# yarns_v03.net
KiCad netlist of a schematic drawn in EAGLE
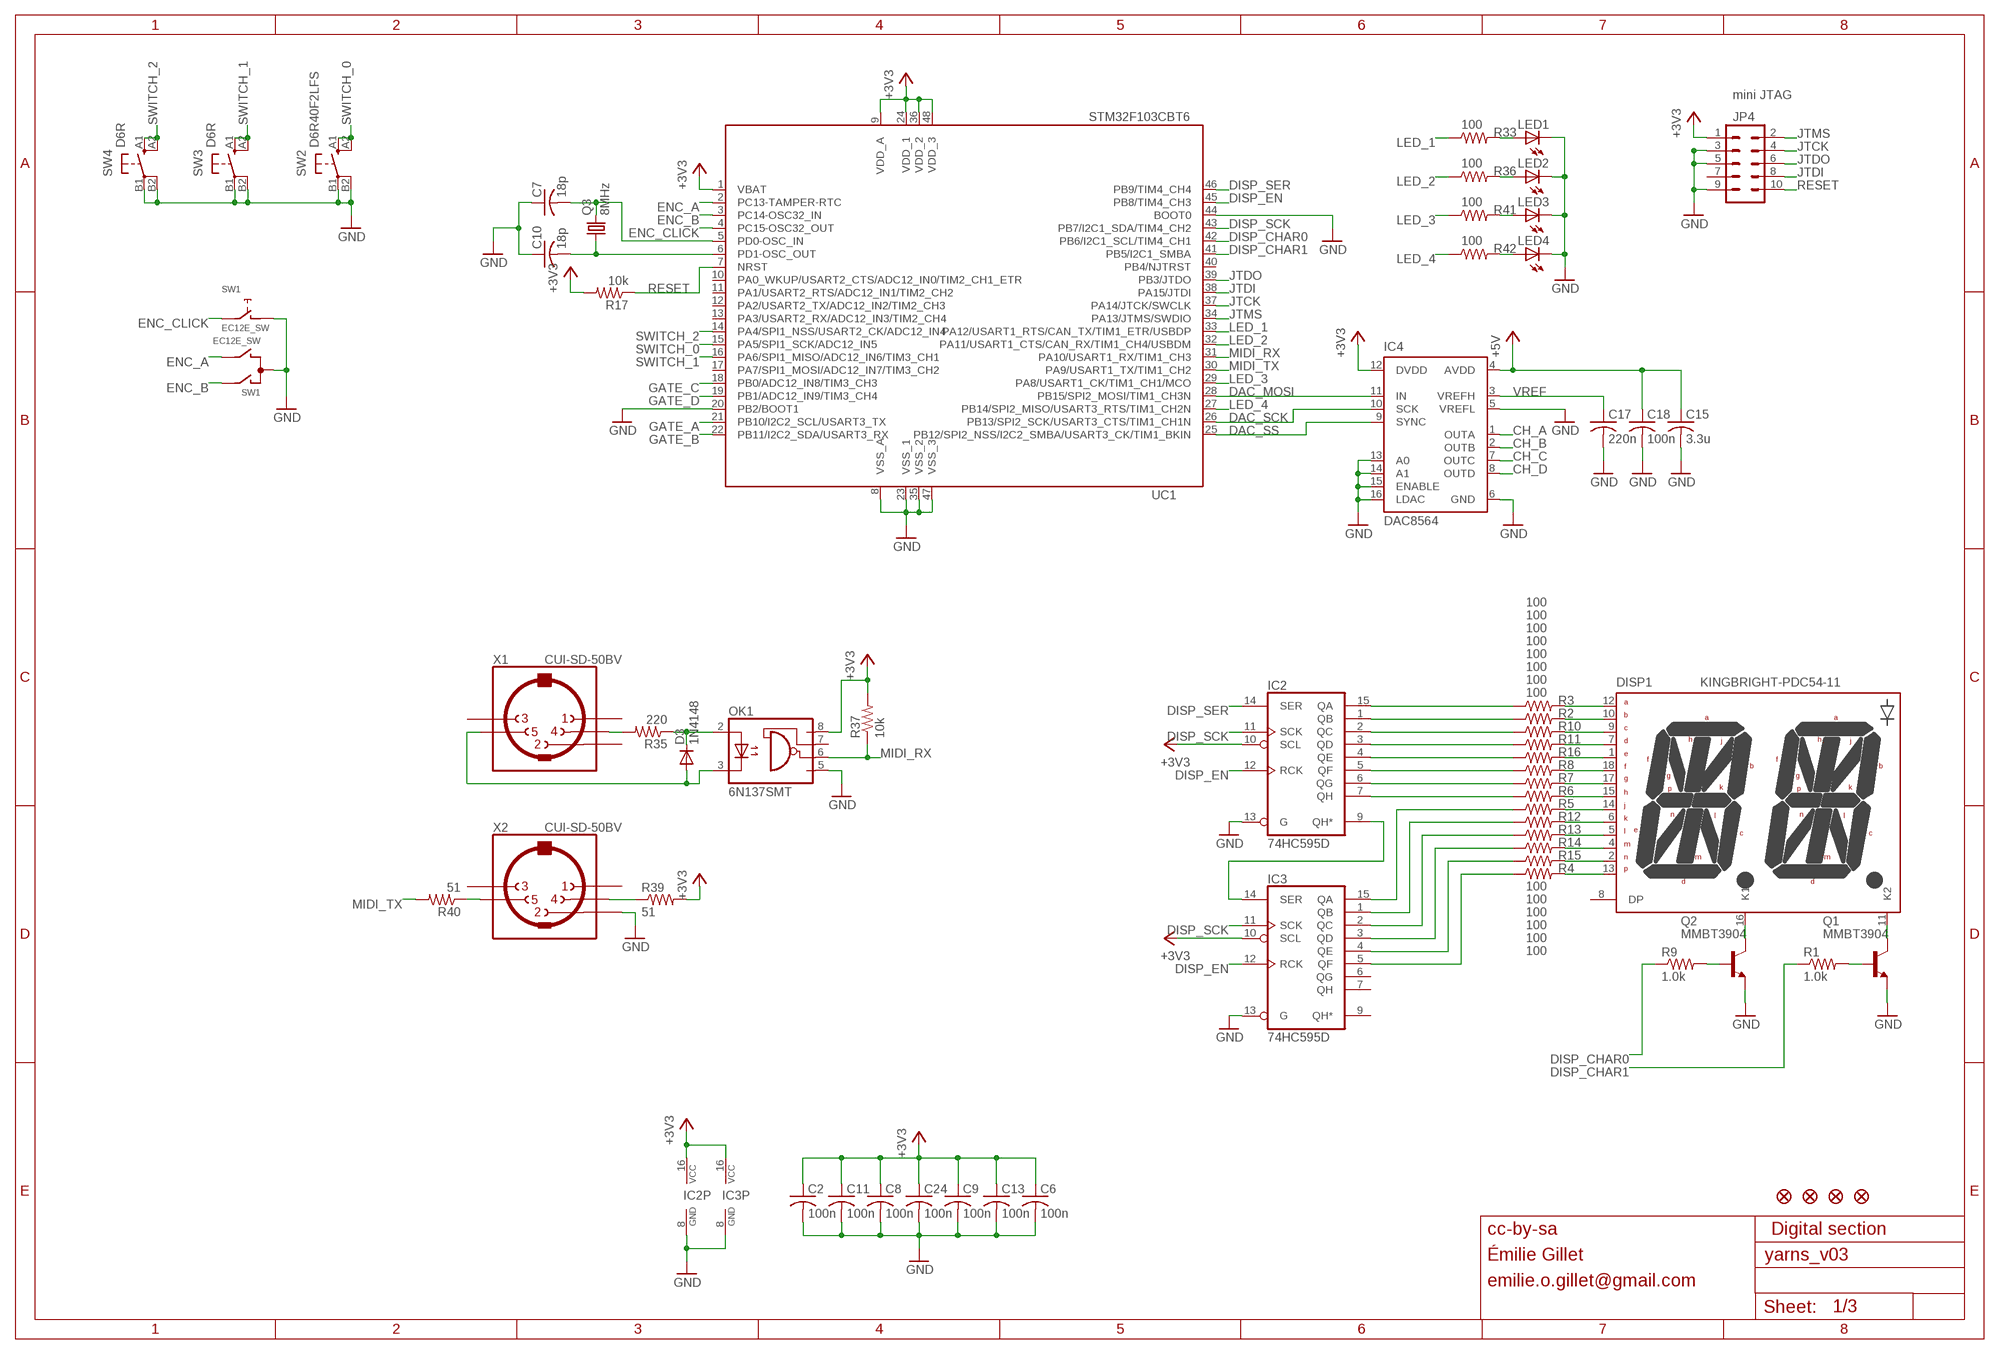
[diagram p0: schematic, sheet 1]
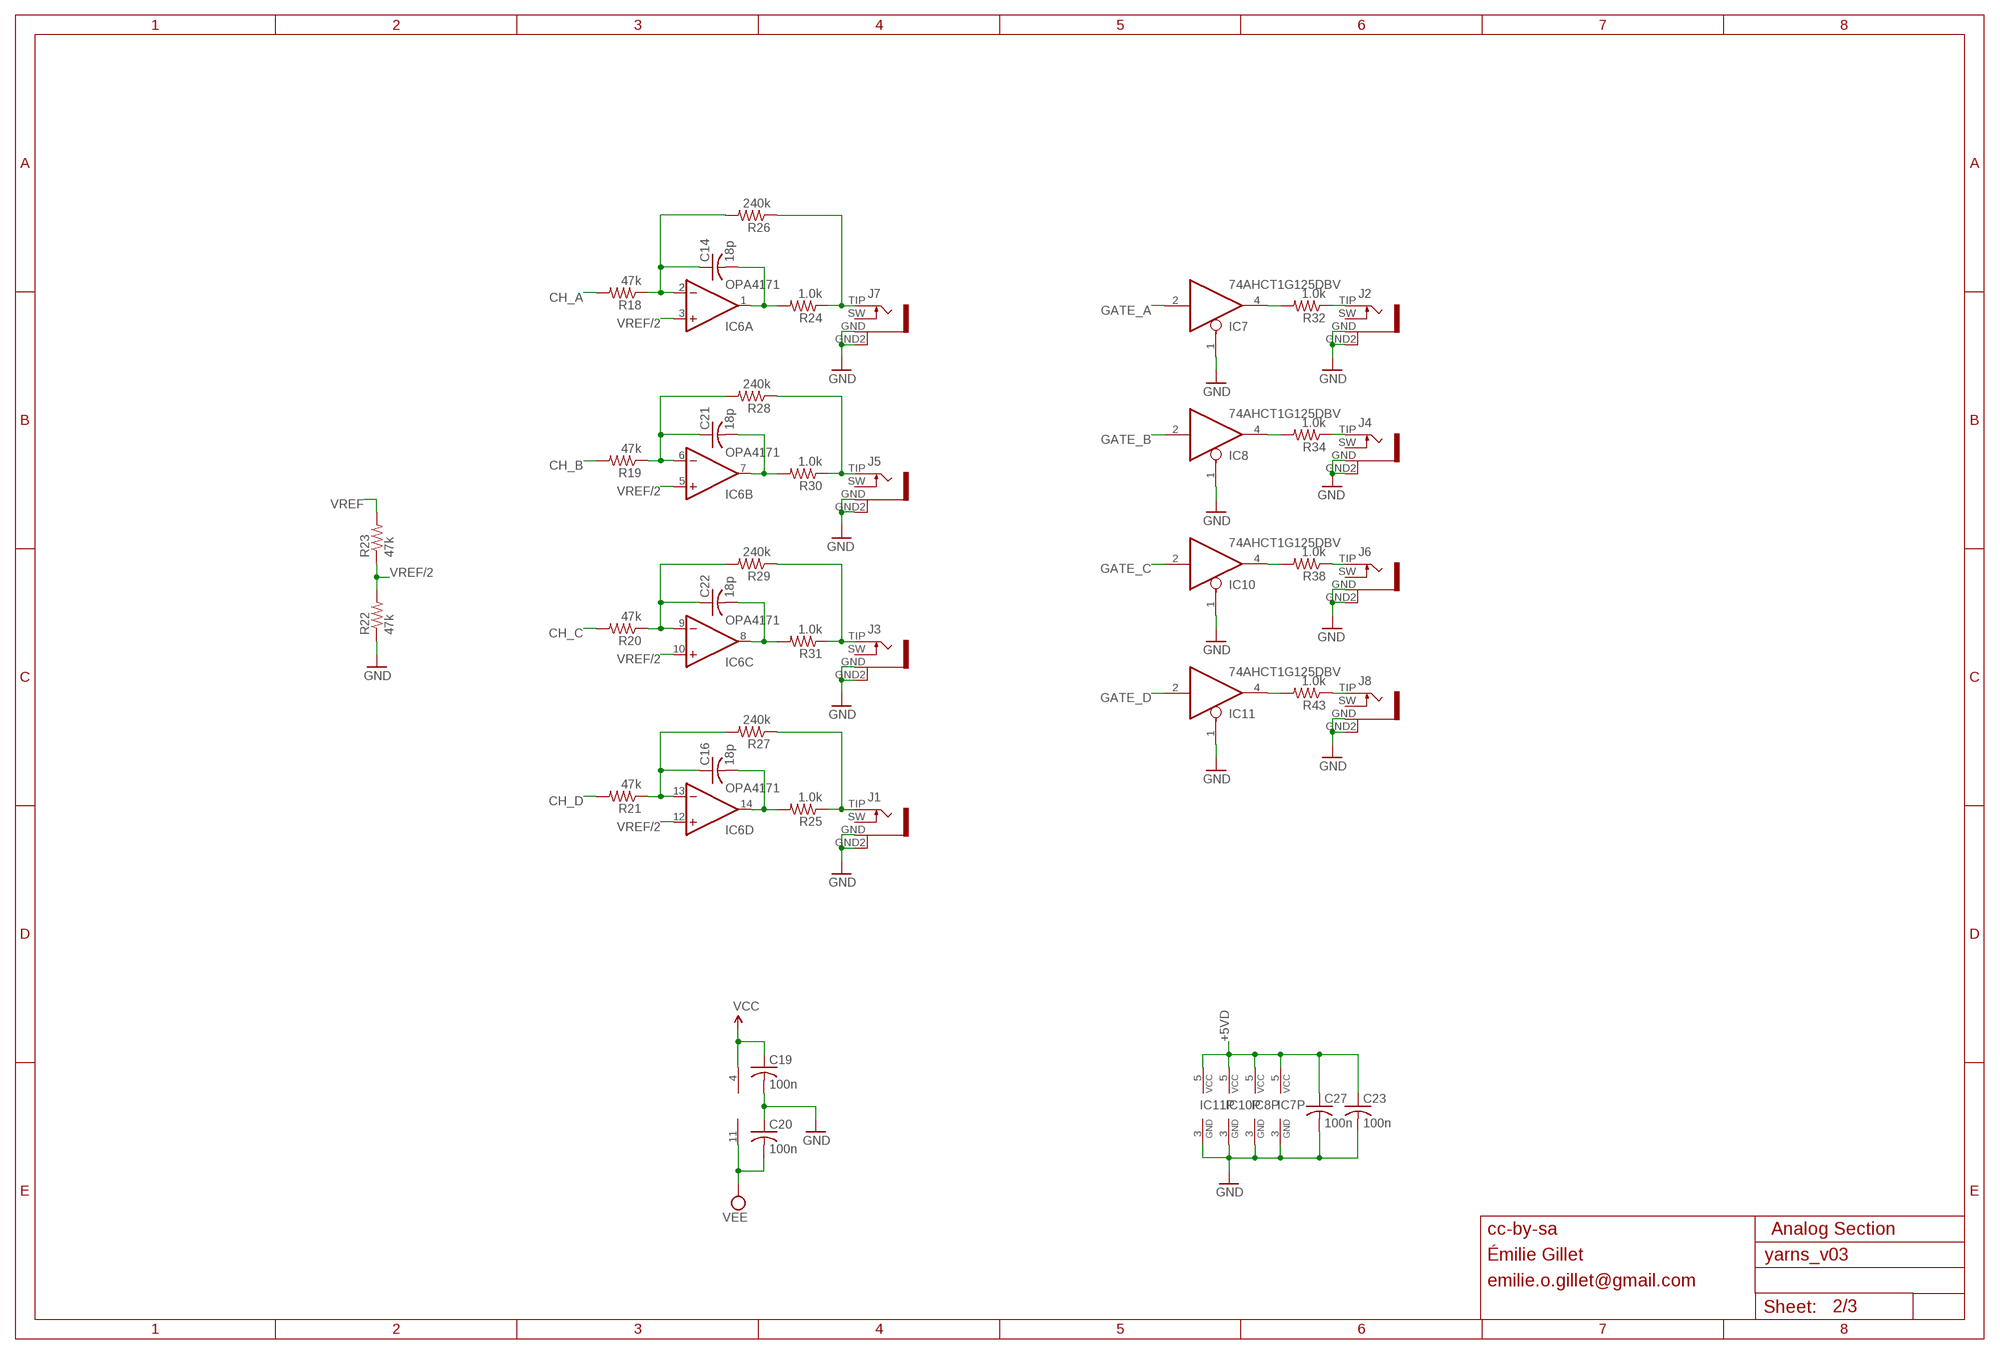
[diagram p1: schematic, sheet 2]
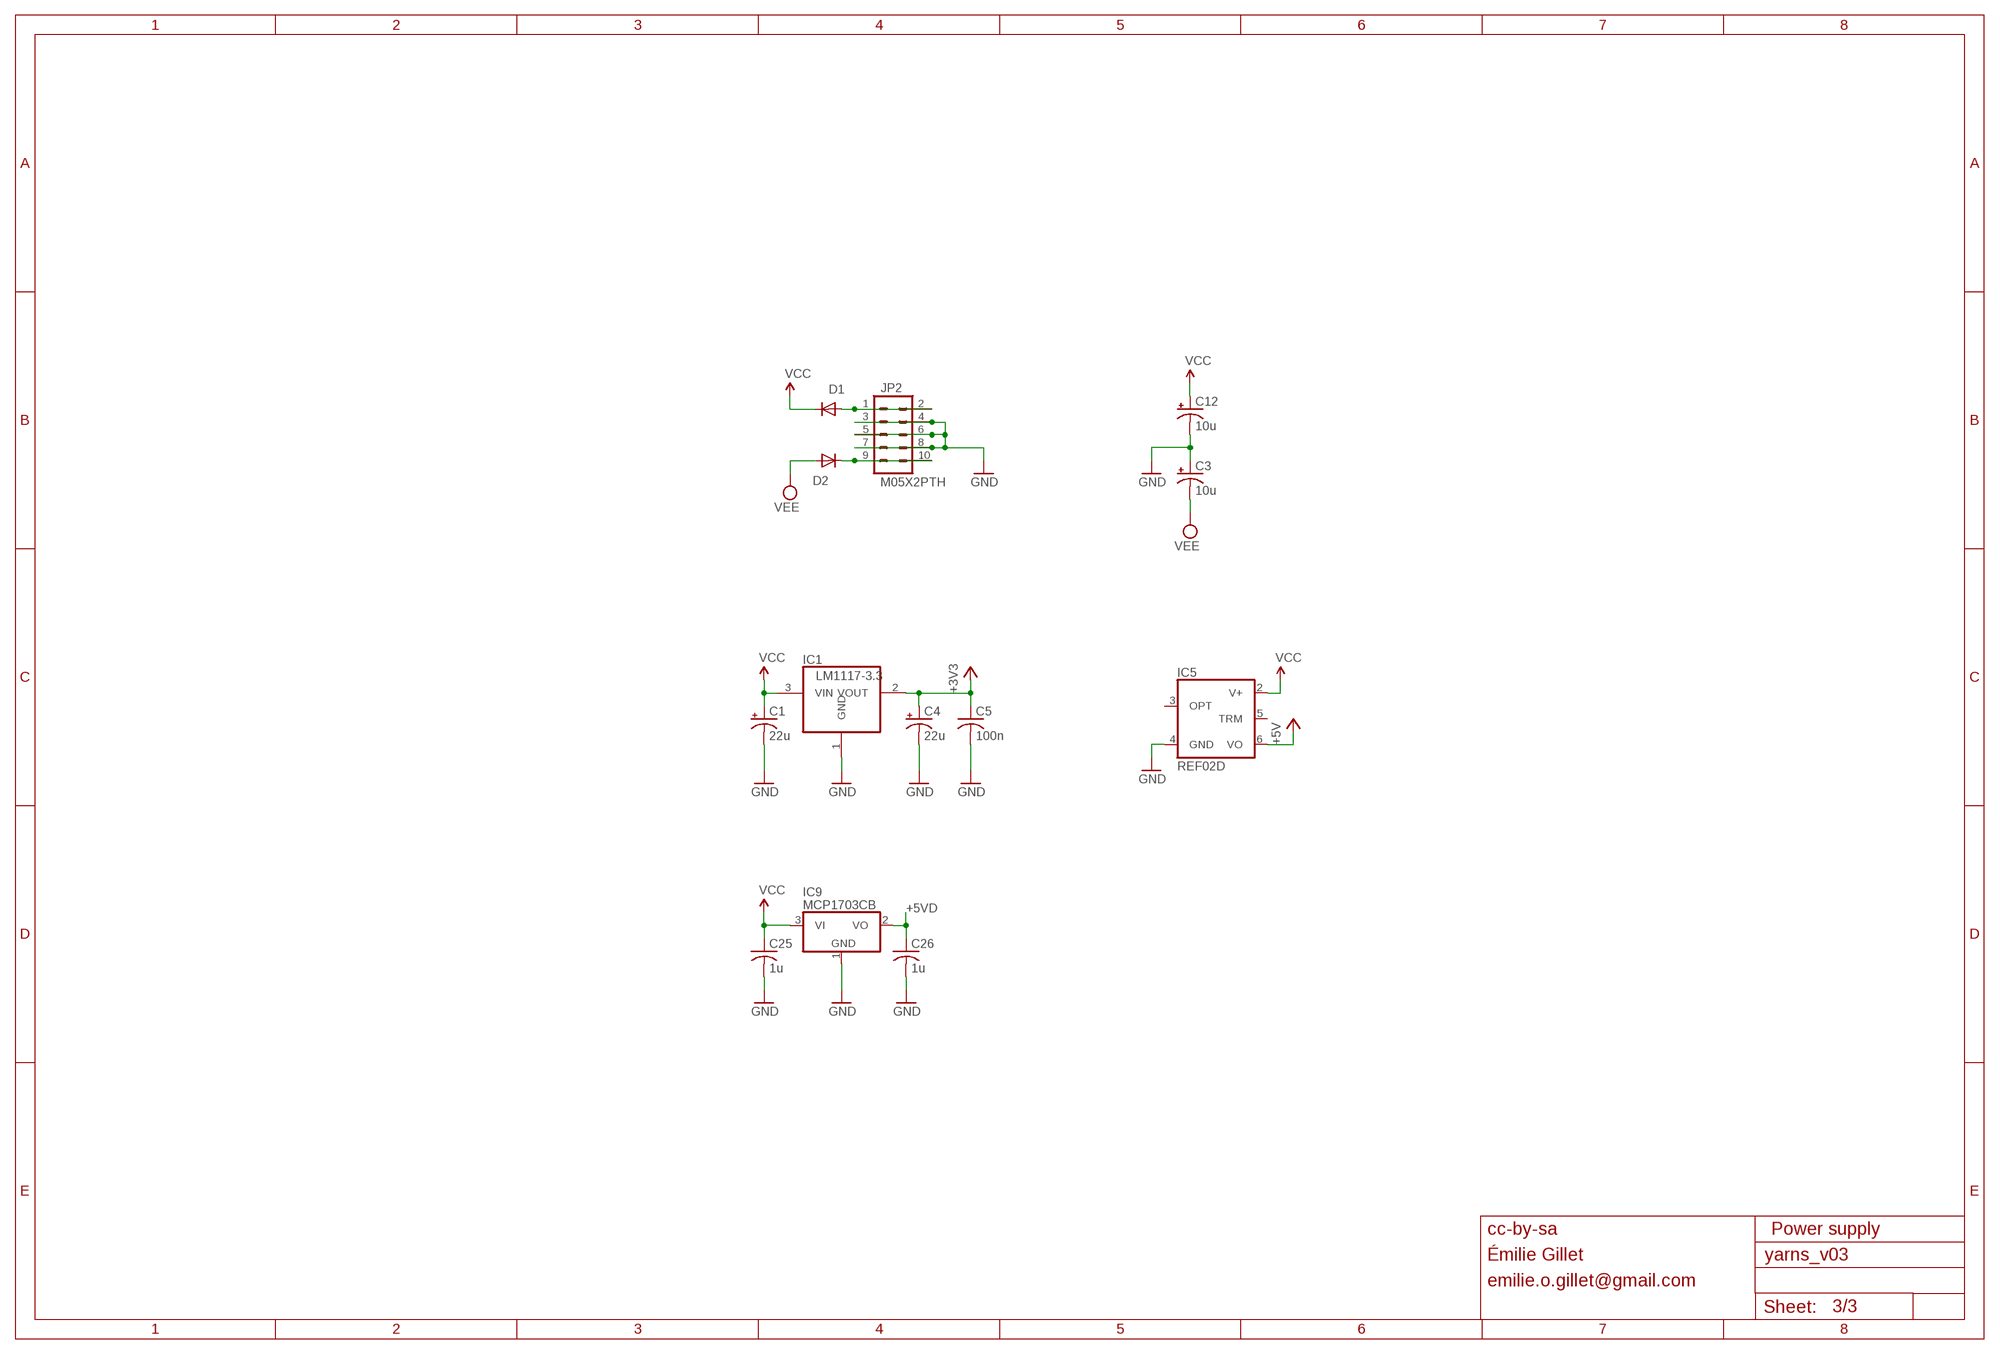
[diagram p2: schematic, sheet 3]

(export (version "E")
  (design (tool "Eeschema 10.0.6"))
  (components
    (comp (ref "C14")
      (value "18p")
      (footprint "eagle-import:C0603")
      (libsource (lib "eagle-import") (part "C-USC0603"))
    )
    (comp (ref "C16")
      (value "18p")
      (footprint "eagle-import:C0603")
      (libsource (lib "eagle-import") (part "C-USC0603"))
    )
    (comp (ref "C19")
      (value "100n")
      (footprint "eagle-import:C0603")
      (libsource (lib "eagle-import") (part "C-USC0603"))
    )
    (comp (ref "C20")
      (value "100n")
      (footprint "eagle-import:C0603")
      (libsource (lib "eagle-import") (part "C-USC0603"))
    )
    (comp (ref "C21")
      (value "18p")
      (footprint "eagle-import:C0603")
      (libsource (lib "eagle-import") (part "C-USC0603"))
    )
    (comp (ref "C22")
      (value "18p")
      (footprint "eagle-import:C0603")
      (libsource (lib "eagle-import") (part "C-USC0603"))
    )
    (comp (ref "C23")
      (value "100n")
      (footprint "eagle-import:C0603")
      (libsource (lib "eagle-import") (part "C-USC0603"))
    )
    (comp (ref "C27")
      (value "100n")
      (footprint "eagle-import:C0603")
      (libsource (lib "eagle-import") (part "C-USC0603"))
    )
    (comp (ref "IC6")
      (value "OPA4171")
      (footprint "eagle-import:SO14")
      (libsource (lib "eagle-import") (part "TL074D"))
    )
    (comp (ref "IC7")
      (value "74AHCT1G125DBV")
      (footprint "eagle-import:SOT23-5")
      (libsource (lib "eagle-import") (part "741G125DBVAHCT"))
    )
    (comp (ref "IC8")
      (value "74AHCT1G125DBV")
      (footprint "eagle-import:SOT23-5")
      (libsource (lib "eagle-import") (part "741G125DBVAHCT"))
    )
    (comp (ref "IC10")
      (value "74AHCT1G125DBV")
      (footprint "eagle-import:SOT23-5")
      (libsource (lib "eagle-import") (part "741G125DBVAHCT"))
    )
    (comp (ref "IC11")
      (value "74AHCT1G125DBV")
      (footprint "eagle-import:SOT23-5")
      (libsource (lib "eagle-import") (part "741G125DBVAHCT"))
    )
    (comp (ref "J1")
      (value "PJ301WQP")
      (footprint "eagle-import:WQP_PJ_301BM")
      (libsource (lib "eagle-import") (part "PJ301WQP"))
    )
    (comp (ref "J2")
      (value "PJ301WQP")
      (footprint "eagle-import:WQP_PJ_301BM")
      (libsource (lib "eagle-import") (part "PJ301WQP"))
    )
    (comp (ref "J3")
      (value "PJ301WQP")
      (footprint "eagle-import:WQP_PJ_301BM")
      (libsource (lib "eagle-import") (part "PJ301WQP"))
    )
    (comp (ref "J4")
      (value "PJ301WQP")
      (footprint "eagle-import:WQP_PJ_301BM")
      (libsource (lib "eagle-import") (part "PJ301WQP"))
    )
    (comp (ref "J5")
      (value "PJ301WQP")
      (footprint "eagle-import:WQP_PJ_301BM")
      (libsource (lib "eagle-import") (part "PJ301WQP"))
    )
    (comp (ref "J6")
      (value "PJ301WQP")
      (footprint "eagle-import:WQP_PJ_301BM")
      (libsource (lib "eagle-import") (part "PJ301WQP"))
    )
    (comp (ref "J7")
      (value "PJ301WQP")
      (footprint "eagle-import:WQP_PJ_301BM")
      (libsource (lib "eagle-import") (part "PJ301WQP"))
    )
    (comp (ref "J8")
      (value "PJ301WQP")
      (footprint "eagle-import:WQP_PJ_301BM")
      (libsource (lib "eagle-import") (part "PJ301WQP"))
    )
    (comp (ref "R18")
      (value "47k")
      (footprint "eagle-import:R0603")
      (libsource (lib "eagle-import") (part "R-US_R0603"))
    )
    (comp (ref "R19")
      (value "47k")
      (footprint "eagle-import:R0603")
      (libsource (lib "eagle-import") (part "R-US_R0603"))
    )
    (comp (ref "R20")
      (value "47k")
      (footprint "eagle-import:R0603")
      (libsource (lib "eagle-import") (part "R-US_R0603"))
    )
    (comp (ref "R21")
      (value "47k")
      (footprint "eagle-import:R0603")
      (libsource (lib "eagle-import") (part "R-US_R0603"))
    )
    (comp (ref "R22")
      (value "47k")
      (footprint "eagle-import:R0603")
      (libsource (lib "eagle-import") (part "R-US_R0603"))
    )
    (comp (ref "R23")
      (value "47k")
      (footprint "eagle-import:R0603")
      (libsource (lib "eagle-import") (part "R-US_R0603"))
    )
    (comp (ref "R24")
      (value "1.0k")
      (footprint "eagle-import:R0603")
      (libsource (lib "eagle-import") (part "R-US_R0603"))
    )
    (comp (ref "R25")
      (value "1.0k")
      (footprint "eagle-import:R0603")
      (libsource (lib "eagle-import") (part "R-US_R0603"))
    )
    (comp (ref "R26")
      (value "240k")
      (footprint "eagle-import:R0603")
      (libsource (lib "eagle-import") (part "R-US_R0603"))
    )
    (comp (ref "R27")
      (value "240k")
      (footprint "eagle-import:R0603")
      (libsource (lib "eagle-import") (part "R-US_R0603"))
    )
    (comp (ref "R28")
      (value "240k")
      (footprint "eagle-import:R0603")
      (libsource (lib "eagle-import") (part "R-US_R0603"))
    )
    (comp (ref "R29")
      (value "240k")
      (footprint "eagle-import:R0603")
      (libsource (lib "eagle-import") (part "R-US_R0603"))
    )
    (comp (ref "R30")
      (value "1.0k")
      (footprint "eagle-import:R0603")
      (libsource (lib "eagle-import") (part "R-US_R0603"))
    )
    (comp (ref "R31")
      (value "1.0k")
      (footprint "eagle-import:R0603")
      (libsource (lib "eagle-import") (part "R-US_R0603"))
    )
    (comp (ref "R32")
      (value "1.0k")
      (footprint "eagle-import:R0603")
      (libsource (lib "eagle-import") (part "R-US_R0603"))
    )
    (comp (ref "R34")
      (value "1.0k")
      (footprint "eagle-import:R0603")
      (libsource (lib "eagle-import") (part "R-US_R0603"))
    )
    (comp (ref "R38")
      (value "1.0k")
      (footprint "eagle-import:R0603")
      (libsource (lib "eagle-import") (part "R-US_R0603"))
    )
    (comp (ref "R43")
      (value "1.0k")
      (footprint "eagle-import:R0603")
      (libsource (lib "eagle-import") (part "R-US_R0603"))
    )
    (comp (ref "C1")
      (value "22u")
      (footprint "eagle-import:PANASONIC_C")
      (libsource (lib "eagle-import") (part "CPOL-USC"))
    )
    (comp (ref "C3")
      (value "10u")
      (footprint "eagle-import:PANASONIC_A")
      (libsource (lib "eagle-import") (part "CPOL-USA"))
    )
    (comp (ref "C4")
      (value "22u")
      (footprint "eagle-import:PANASONIC_C")
      (libsource (lib "eagle-import") (part "CPOL-USC"))
    )
    (comp (ref "C5")
      (value "100n")
      (footprint "eagle-import:C0603")
      (libsource (lib "eagle-import") (part "C-USC0603"))
    )
    (comp (ref "C12")
      (value "10u")
      (footprint "eagle-import:PANASONIC_A")
      (libsource (lib "eagle-import") (part "CPOL-USA"))
    )
    (comp (ref "C25")
      (value "1u")
      (footprint "eagle-import:C0603")
      (libsource (lib "eagle-import") (part "C-USC0603"))
    )
    (comp (ref "C26")
      (value "1u")
      (footprint "eagle-import:C0603")
      (libsource (lib "eagle-import") (part "C-USC0603"))
    )
    (comp (ref "D1")
      (value "1N5819HW")
      (footprint "eagle-import:SOD123")
      (libsource (lib "eagle-import") (part "DIODE-SOD123"))
    )
    (comp (ref "D2")
      (value "1N5819HW")
      (footprint "eagle-import:SOD123")
      (libsource (lib "eagle-import") (part "DIODE-SOD123"))
    )
    (comp (ref "IC1")
      (value "LM1117-3.3")
      (footprint "eagle-import:SOT223")
      (libsource (lib "eagle-import") (part "REG1117"))
    )
    (comp (ref "IC5")
      (value "REF02D")
      (footprint "eagle-import:SO08")
      (libsource (lib "eagle-import") (part "REF02D"))
    )
    (comp (ref "IC9")
      (value "MCP1703CB")
      (footprint "eagle-import:SOT23")
      (libsource (lib "eagle-import") (part "MCP1703CB"))
    )
    (comp (ref "JP2")
      (value "M05X2PTH")
      (footprint "eagle-import:AVR_ICSP")
      (libsource (lib "eagle-import") (part "M05X2PTH"))
    )
    (comp (ref "C2")
      (value "100n")
      (footprint "eagle-import:C0603")
      (libsource (lib "eagle-import") (part "C-USC0603"))
    )
    (comp (ref "C6")
      (value "100n")
      (footprint "eagle-import:C0603")
      (libsource (lib "eagle-import") (part "C-USC0603"))
    )
    (comp (ref "C7")
      (value "18p")
      (footprint "eagle-import:C0603")
      (libsource (lib "eagle-import") (part "C-USC0603"))
    )
    (comp (ref "C8")
      (value "100n")
      (footprint "eagle-import:C0603")
      (libsource (lib "eagle-import") (part "C-USC0603"))
    )
    (comp (ref "C9")
      (value "100n")
      (footprint "eagle-import:C0603")
      (libsource (lib "eagle-import") (part "C-USC0603"))
    )
    (comp (ref "C10")
      (value "18p")
      (footprint "eagle-import:C0603")
      (libsource (lib "eagle-import") (part "C-USC0603"))
    )
    (comp (ref "C11")
      (value "100n")
      (footprint "eagle-import:C0603")
      (libsource (lib "eagle-import") (part "C-USC0603"))
    )
    (comp (ref "C13")
      (value "100n")
      (footprint "eagle-import:C0603")
      (libsource (lib "eagle-import") (part "C-USC0603"))
    )
    (comp (ref "C15")
      (value "3.3u")
      (footprint "eagle-import:C0603")
      (libsource (lib "eagle-import") (part "C-USC0603"))
    )
    (comp (ref "C17")
      (value "220n")
      (footprint "eagle-import:C0603")
      (libsource (lib "eagle-import") (part "C-USC0603"))
    )
    (comp (ref "C18")
      (value "100n")
      (footprint "eagle-import:C0603")
      (libsource (lib "eagle-import") (part "C-USC0603"))
    )
    (comp (ref "C24")
      (value "100n")
      (footprint "eagle-import:C0603")
      (libsource (lib "eagle-import") (part "C-USC0603"))
    )
    (comp (ref "D3")
      (value "1N4148")
      (footprint "eagle-import:SOD323-W")
      (libsource (lib "eagle-import") (part "DIODE-SOD323-W"))
    )
    (comp (ref "DISP1")
      (value "KINGBRIGHT-PDC54-11")
      (footprint "eagle-import:PDC54")
      (libsource (lib "eagle-import") (part "KINGBRIGHT-PDC54-11"))
    )
    (comp (ref "F1")
      (value "FIDUCIAL1X2")
      (footprint "eagle-import:FIDUCIAL-1X2")
      (libsource (lib "eagle-import") (part "FIDUCIAL1X2"))
    )
    (comp (ref "F3")
      (value "FIDUCIAL1X2")
      (footprint "eagle-import:FIDUCIAL-1X2")
      (libsource (lib "eagle-import") (part "FIDUCIAL1X2"))
    )
    (comp (ref "F5")
      (value "FIDUCIAL1X2")
      (footprint "eagle-import:FIDUCIAL-1X2")
      (libsource (lib "eagle-import") (part "FIDUCIAL1X2"))
    )
    (comp (ref "F6")
      (value "FIDUCIAL1X2")
      (footprint "eagle-import:FIDUCIAL-1X2")
      (libsource (lib "eagle-import") (part "FIDUCIAL1X2"))
    )
    (comp (ref "IC2")
      (value "74HC595D")
      (footprint "eagle-import:SO16")
      (libsource (lib "eagle-import") (part "74595DHC"))
    )
    (comp (ref "IC3")
      (value "74HC595D")
      (footprint "eagle-import:SO16")
      (libsource (lib "eagle-import") (part "74595DHC"))
    )
    (comp (ref "IC4")
      (value "DAC8564")
      (footprint "eagle-import:SOP65P640X110-16N")
      (libsource (lib "eagle-import") (part "DAC8564"))
    )
    (comp (ref "JP4")
      (value "M05X2MINIJTAG")
      (footprint "eagle-import:2X5-1.27")
      (libsource (lib "eagle-import") (part "M05X2MINIJTAG"))
    )
    (comp (ref "LED1")
      (value "LED3MM")
      (footprint "eagle-import:LED3MM")
      (libsource (lib "eagle-import") (part "LED3MM"))
    )
    (comp (ref "LED2")
      (value "LED3MM")
      (footprint "eagle-import:LED3MM")
      (libsource (lib "eagle-import") (part "LED3MM"))
    )
    (comp (ref "LED3")
      (value "LED3MM")
      (footprint "eagle-import:LED3MM")
      (libsource (lib "eagle-import") (part "LED3MM"))
    )
    (comp (ref "LED4")
      (value "LED3MM")
      (footprint "eagle-import:LED3MM")
      (libsource (lib "eagle-import") (part "LED3MM"))
    )
    (comp (ref "OK1")
      (value "6N137SMT")
      (footprint "eagle-import:DIL8-SMD")
      (libsource (lib "eagle-import") (part "6N137SMT"))
    )
    (comp (ref "Q1")
      (value "MMBT3904")
      (footprint "eagle-import:SOT23-BEC")
      (libsource (lib "eagle-import") (part "-NPN-SOT23-BECMMBT3904LT1"))
    )
    (comp (ref "Q2")
      (value "MMBT3904")
      (footprint "eagle-import:SOT23-BEC")
      (libsource (lib "eagle-import") (part "-NPN-SOT23-BECMMBT3904LT1"))
    )
    (comp (ref "Q3")
      (value "8MHz")
      (footprint "eagle-import:HC49UP")
      (libsource (lib "eagle-import") (part "CRYSTALHC49UP"))
    )
    (comp (ref "R1")
      (value "1.0k")
      (footprint "eagle-import:R0603")
      (libsource (lib "eagle-import") (part "R-US_R0603"))
    )
    (comp (ref "R2")
      (value "100")
      (footprint "eagle-import:R0603")
      (libsource (lib "eagle-import") (part "R-US_R0603"))
    )
    (comp (ref "R3")
      (value "100")
      (footprint "eagle-import:R0603")
      (libsource (lib "eagle-import") (part "R-US_R0603"))
    )
    (comp (ref "R4")
      (value "100")
      (footprint "eagle-import:R0603")
      (libsource (lib "eagle-import") (part "R-US_R0603"))
    )
    (comp (ref "R5")
      (value "100")
      (footprint "eagle-import:R0603")
      (libsource (lib "eagle-import") (part "R-US_R0603"))
    )
    (comp (ref "R6")
      (value "100")
      (footprint "eagle-import:R0603")
      (libsource (lib "eagle-import") (part "R-US_R0603"))
    )
    (comp (ref "R7")
      (value "100")
      (footprint "eagle-import:R0603")
      (libsource (lib "eagle-import") (part "R-US_R0603"))
    )
    (comp (ref "R8")
      (value "100")
      (footprint "eagle-import:R0603")
      (libsource (lib "eagle-import") (part "R-US_R0603"))
    )
    (comp (ref "R9")
      (value "1.0k")
      (footprint "eagle-import:R0603")
      (libsource (lib "eagle-import") (part "R-US_R0603"))
    )
    (comp (ref "R10")
      (value "100")
      (footprint "eagle-import:R0603")
      (libsource (lib "eagle-import") (part "R-US_R0603"))
    )
    (comp (ref "R11")
      (value "100")
      (footprint "eagle-import:R0603")
      (libsource (lib "eagle-import") (part "R-US_R0603"))
    )
    (comp (ref "R12")
      (value "100")
      (footprint "eagle-import:R0603")
      (libsource (lib "eagle-import") (part "R-US_R0603"))
    )
    (comp (ref "R13")
      (value "100")
      (footprint "eagle-import:R0603")
      (libsource (lib "eagle-import") (part "R-US_R0603"))
    )
    (comp (ref "R14")
      (value "100")
      (footprint "eagle-import:R0603")
      (libsource (lib "eagle-import") (part "R-US_R0603"))
    )
    (comp (ref "R15")
      (value "100")
      (footprint "eagle-import:R0603")
      (libsource (lib "eagle-import") (part "R-US_R0603"))
    )
    (comp (ref "R16")
      (value "100")
      (footprint "eagle-import:R0603")
      (libsource (lib "eagle-import") (part "R-US_R0603"))
    )
    (comp (ref "R17")
      (value "10k")
      (footprint "eagle-import:R0603")
      (libsource (lib "eagle-import") (part "R-US_R0603"))
    )
    (comp (ref "R33")
      (value "100")
      (footprint "eagle-import:R0603")
      (libsource (lib "eagle-import") (part "R-US_R0603"))
    )
    (comp (ref "R35")
      (value "220")
      (footprint "eagle-import:R0603")
      (libsource (lib "eagle-import") (part "R-US_R0603"))
    )
    (comp (ref "R36")
      (value "100")
      (footprint "eagle-import:R0603")
      (libsource (lib "eagle-import") (part "R-US_R0603"))
    )
    (comp (ref "R37")
      (value "10k")
      (footprint "eagle-import:R0603")
      (libsource (lib "eagle-import") (part "R-US_R0603"))
    )
    (comp (ref "R39")
      (value "51")
      (footprint "eagle-import:R0603")
      (libsource (lib "eagle-import") (part "R-US_R0603"))
    )
    (comp (ref "R40")
      (value "51")
      (footprint "eagle-import:R0603")
      (libsource (lib "eagle-import") (part "R-US_R0603"))
    )
    (comp (ref "R41")
      (value "100")
      (footprint "eagle-import:R0603")
      (libsource (lib "eagle-import") (part "R-US_R0603"))
    )
    (comp (ref "R42")
      (value "100")
      (footprint "eagle-import:R0603")
      (libsource (lib "eagle-import") (part "R-US_R0603"))
    )
    (comp (ref "SW1")
      (value "EC12E_SW")
      (footprint "eagle-import:ALPS_EC12E_SW")
      (libsource (lib "eagle-import") (part "EC12E_SW"))
    )
    (comp (ref "SW2")
      (value "D6R40F2LFS")
      (footprint "eagle-import:D6R")
      (libsource (lib "eagle-import") (part "D6R"))
    )
    (comp (ref "SW3")
      (value "D6R")
      (footprint "eagle-import:D6R")
      (libsource (lib "eagle-import") (part "D6R"))
    )
    (comp (ref "SW4")
      (value "D6R")
      (footprint "eagle-import:D6R")
      (libsource (lib "eagle-import") (part "D6R"))
    )
    (comp (ref "UC1")
      (value "STM32F103CBT6")
      (footprint "eagle-import:LQFP48")
      (libsource (lib "eagle-import") (part "STM32F103CB"))
    )
    (comp (ref "X1")
      (value "CUI-SD-50BV")
      (footprint "eagle-import:SD-50BV")
      (libsource (lib "eagle-import") (part "MAB5SHCUI-SD-50BV"))
    )
    (comp (ref "X2")
      (value "CUI-SD-50BV")
      (footprint "eagle-import:SD-50BV")
      (libsource (lib "eagle-import") (part "MAB5SHCUI-SD-50BV"))
    )
  )
  (nets
    (net (code "1") (name "+3V3") (class "Default")
      (node (ref "C11") (pin "1") (pinfunction "1_1") (pintype "passive"))
      (node (ref "C13") (pin "1") (pinfunction "1_1") (pintype "passive"))
      (node (ref "C2") (pin "1") (pinfunction "1_1") (pintype "passive"))
      (node (ref "C24") (pin "1") (pinfunction "1_1") (pintype "passive"))
      (node (ref "C4") (pin "+") (pinfunction "+_+") (pintype "passive"))
      (node (ref "C5") (pin "1") (pinfunction "1_1") (pintype "passive"))
      (node (ref "C6") (pin "1") (pinfunction "1_1") (pintype "passive"))
      (node (ref "C8") (pin "1") (pinfunction "1_1") (pintype "passive"))
      (node (ref "C9") (pin "1") (pinfunction "1_1") (pintype "passive"))
      (node (ref "IC1") (pin "2") (pinfunction "VOUT_2") (pintype "output"))
      (node (ref "IC2") (pin "10") (pinfunction "SCL_10") (pintype "input"))
      (node (ref "IC2") (pin "16") (pinfunction "VCC_16") (pintype "power_in"))
      (node (ref "IC3") (pin "10") (pinfunction "SCL_10") (pintype "input"))
      (node (ref "IC3") (pin "16") (pinfunction "VCC_16") (pintype "power_in"))
      (node (ref "IC4") (pin "12") (pinfunction "DVDD_12") (pintype "power_in"))
      (node (ref "JP4") (pin "1") (pinfunction "1_1") (pintype "passive"))
      (node (ref "OK1") (pin "8") (pinfunction "VCC_8") (pintype "passive"))
      (node (ref "R17") (pin "2") (pinfunction "2_2") (pintype "passive"))
      (node (ref "R37") (pin "2") (pinfunction "2_2") (pintype "passive"))
      (node (ref "R39") (pin "2") (pinfunction "2_2") (pintype "passive"))
      (node (ref "UC1") (pin "1") (pinfunction "VBAT_1") (pintype "power_in"))
      (node (ref "UC1") (pin "24") (pinfunction "VDD_1_24") (pintype "power_in"))
      (node (ref "UC1") (pin "36") (pinfunction "VDD_2_36") (pintype "power_in"))
      (node (ref "UC1") (pin "48") (pinfunction "VDD_3_48") (pintype "power_in"))
      (node (ref "UC1") (pin "9") (pinfunction "VDD_A_9") (pintype "power_in"))
    )
    (net (code "2") (name "+5V") (class "Default")
      (node (ref "C15") (pin "1") (pinfunction "1_1") (pintype "passive"))
      (node (ref "C18") (pin "1") (pinfunction "1_1") (pintype "passive"))
      (node (ref "IC4") (pin "4") (pinfunction "AVDD_4") (pintype "power_in"))
      (node (ref "IC5") (pin "6") (pinfunction "VO_6") (pintype "output"))
    )
    (net (code "3") (name "+5VD") (class "Default")
      (node (ref "C23") (pin "1") (pinfunction "1_1") (pintype "passive"))
      (node (ref "C26") (pin "1") (pinfunction "1_1") (pintype "passive"))
      (node (ref "C27") (pin "1") (pinfunction "1_1") (pintype "passive"))
      (node (ref "IC10") (pin "5") (pinfunction "VCC_5") (pintype "power_in"))
      (node (ref "IC11") (pin "5") (pinfunction "VCC_5") (pintype "power_in"))
      (node (ref "IC7") (pin "5") (pinfunction "VCC_5") (pintype "power_in"))
      (node (ref "IC8") (pin "5") (pinfunction "VCC_5") (pintype "power_in"))
      (node (ref "IC9") (pin "2") (pinfunction "VO_2") (pintype "passive"))
    )
    (net (code "4") (name "CH_A") (class "Default")
      (node (ref "IC4") (pin "1") (pinfunction "OUTA_1") (pintype "output"))
      (node (ref "R18") (pin "2") (pinfunction "2_2") (pintype "passive"))
    )
    (net (code "5") (name "CH_B") (class "Default")
      (node (ref "IC4") (pin "2") (pinfunction "OUTB_2") (pintype "output"))
      (node (ref "R19") (pin "2") (pinfunction "2_2") (pintype "passive"))
    )
    (net (code "6") (name "CH_C") (class "Default")
      (node (ref "IC4") (pin "7") (pinfunction "OUTC_7") (pintype "output"))
      (node (ref "R20") (pin "2") (pinfunction "2_2") (pintype "passive"))
    )
    (net (code "7") (name "CH_D") (class "Default")
      (node (ref "IC4") (pin "8") (pinfunction "OUTD_8") (pintype "output"))
      (node (ref "R21") (pin "2") (pinfunction "2_2") (pintype "passive"))
    )
    (net (code "8") (name "DAC_MOSI") (class "Default")
      (node (ref "IC4") (pin "11") (pinfunction "IN_11") (pintype "input"))
      (node (ref "UC1") (pin "28") (pinfunction "PB15/SPI2_MOSI/TIM1_CH3N_28") (pintype "input"))
    )
    (net (code "9") (name "DAC_SCK") (class "Default")
      (node (ref "IC4") (pin "10") (pinfunction "SCK_10") (pintype "input"))
      (node (ref "UC1") (pin "26") (pinfunction "PB13/SPI2_SCK/USART3_CTS/TIM1_CH1N_26") (pintype "input"))
    )
    (net (code "10") (name "DAC_SS") (class "Default")
      (node (ref "IC4") (pin "9") (pinfunction "SYNC_9") (pintype "input"))
      (node (ref "UC1") (pin "25") (pinfunction "PB12/SPI2_NSS/I2C2_SMBA/USART3_CK/TIM1_BKIN_25") (pintype "input"))
    )
    (net (code "11") (name "DISP_CHAR0") (class "Default")
      (node (ref "R9") (pin "1") (pinfunction "1_1") (pintype "passive"))
      (node (ref "UC1") (pin "42") (pinfunction "PB6/I2C1_SCL/TIM4_CH1_42") (pintype "input"))
    )
    (net (code "12") (name "DISP_CHAR1") (class "Default")
      (node (ref "R1") (pin "1") (pinfunction "1_1") (pintype "passive"))
      (node (ref "UC1") (pin "41") (pinfunction "PB5/I2C1_SMBA_41") (pintype "input"))
    )
    (net (code "13") (name "DISP_EN") (class "Default")
      (node (ref "IC2") (pin "12") (pinfunction "RCK_12") (pintype "input"))
      (node (ref "IC3") (pin "12") (pinfunction "RCK_12") (pintype "input"))
      (node (ref "UC1") (pin "45") (pinfunction "PB8/TIM4_CH3_45") (pintype "bidirectional"))
    )
    (net (code "14") (name "DISP_SCK") (class "Default")
      (node (ref "IC2") (pin "11") (pinfunction "SCK_11") (pintype "input"))
      (node (ref "IC3") (pin "11") (pinfunction "SCK_11") (pintype "input"))
      (node (ref "UC1") (pin "43") (pinfunction "PB7/I2C1_SDA/TIM4_CH2_43") (pintype "bidirectional"))
    )
    (net (code "15") (name "DISP_SER") (class "Default")
      (node (ref "IC2") (pin "14") (pinfunction "SER_14") (pintype "input"))
      (node (ref "UC1") (pin "46") (pinfunction "PB9/TIM4_CH4_46") (pintype "input"))
    )
    (net (code "16") (name "ENC_A") (class "Default")
      (node (ref "SW1") (pin "B") (pinfunction "B_B") (pintype "passive"))
      (node (ref "UC1") (pin "2") (pinfunction "PC13-TAMPER-RTC_2") (pintype "input"))
    )
    (net (code "17") (name "ENC_B") (class "Default")
      (node (ref "SW1") (pin "A") (pinfunction "A_A") (pintype "passive"))
      (node (ref "UC1") (pin "3") (pinfunction "PC14-OSC32_IN_3") (pintype "input"))
    )
    (net (code "18") (name "ENC_CLICK") (class "Default")
      (node (ref "SW1") (pin "E") (pinfunction "2_E") (pintype "passive"))
      (node (ref "UC1") (pin "4") (pinfunction "PC15-OSC32_OUT_4") (pintype "input"))
    )
    (net (code "19") (name "GATE_A") (class "Default")
      (node (ref "IC7") (pin "2") (pinfunction "I_2") (pintype "input"))
      (node (ref "UC1") (pin "21") (pinfunction "PB10/I2C2_SCL/USART3_TX_21") (pintype "input"))
    )
    (net (code "20") (name "GATE_B") (class "Default")
      (node (ref "IC8") (pin "2") (pinfunction "I_2") (pintype "input"))
      (node (ref "UC1") (pin "22") (pinfunction "PB11/I2C2_SDA/USART3_RX_22") (pintype "input"))
    )
    (net (code "21") (name "GATE_C") (class "Default")
      (node (ref "IC10") (pin "2") (pinfunction "I_2") (pintype "input"))
      (node (ref "UC1") (pin "18") (pinfunction "PB0/ADC12_IN8/TIM3_CH3_18") (pintype "bidirectional"))
    )
    (net (code "22") (name "GATE_D") (class "Default")
      (node (ref "IC11") (pin "2") (pinfunction "I_2") (pintype "input"))
      (node (ref "UC1") (pin "19") (pinfunction "PB1/ADC12_IN9/TIM3_CH4_19") (pintype "bidirectional"))
    )
    (net (code "23") (name "GND") (class "Default")
      (node (ref "C1") (pin "-") (pinfunction "-_-") (pintype "passive"))
      (node (ref "C10") (pin "1") (pinfunction "1_1") (pintype "passive"))
      (node (ref "C11") (pin "2") (pinfunction "2_2") (pintype "passive"))
      (node (ref "C12") (pin "-") (pinfunction "-_-") (pintype "passive"))
      (node (ref "C13") (pin "2") (pinfunction "2_2") (pintype "passive"))
      (node (ref "C15") (pin "2") (pinfunction "2_2") (pintype "passive"))
      (node (ref "C17") (pin "2") (pinfunction "2_2") (pintype "passive"))
      (node (ref "C18") (pin "2") (pinfunction "2_2") (pintype "passive"))
      (node (ref "C19") (pin "2") (pinfunction "2_2") (pintype "passive"))
      (node (ref "C2") (pin "2") (pinfunction "2_2") (pintype "passive"))
      (node (ref "C20") (pin "1") (pinfunction "1_1") (pintype "passive"))
      (node (ref "C23") (pin "2") (pinfunction "2_2") (pintype "passive"))
      (node (ref "C24") (pin "2") (pinfunction "2_2") (pintype "passive"))
      (node (ref "C25") (pin "2") (pinfunction "2_2") (pintype "passive"))
      (node (ref "C26") (pin "2") (pinfunction "2_2") (pintype "passive"))
      (node (ref "C27") (pin "2") (pinfunction "2_2") (pintype "passive"))
      (node (ref "C3") (pin "+") (pinfunction "+_+") (pintype "passive"))
      (node (ref "C4") (pin "-") (pinfunction "-_-") (pintype "passive"))
      (node (ref "C5") (pin "2") (pinfunction "2_2") (pintype "passive"))
      (node (ref "C6") (pin "2") (pinfunction "2_2") (pintype "passive"))
      (node (ref "C7") (pin "1") (pinfunction "1_1") (pintype "passive"))
      (node (ref "C8") (pin "2") (pinfunction "2_2") (pintype "passive"))
      (node (ref "C9") (pin "2") (pinfunction "2_2") (pintype "passive"))
      (node (ref "IC1") (pin "1") (pinfunction "GND_1") (pintype "power_in"))
      (node (ref "IC10") (pin "1") (pinfunction "OE_1") (pintype "input"))
      (node (ref "IC10") (pin "3") (pinfunction "GND_3") (pintype "power_in"))
      (node (ref "IC11") (pin "1") (pinfunction "OE_1") (pintype "input"))
      (node (ref "IC11") (pin "3") (pinfunction "GND_3") (pintype "power_in"))
      (node (ref "IC2") (pin "13") (pinfunction "G_13") (pintype "input"))
      (node (ref "IC2") (pin "8") (pinfunction "GND_8") (pintype "power_in"))
      (node (ref "IC3") (pin "13") (pinfunction "G_13") (pintype "input"))
      (node (ref "IC3") (pin "8") (pinfunction "GND_8") (pintype "power_in"))
      (node (ref "IC4") (pin "13") (pinfunction "A0_13") (pintype "input"))
      (node (ref "IC4") (pin "14") (pinfunction "A1_14") (pintype "input"))
      (node (ref "IC4") (pin "15") (pinfunction "ENABLE_15") (pintype "input"))
      (node (ref "IC4") (pin "16") (pinfunction "LDAC_16") (pintype "input"))
      (node (ref "IC4") (pin "5") (pinfunction "VREFL_5") (pintype "bidirectional"))
      (node (ref "IC4") (pin "6") (pinfunction "GND_6") (pintype "power_in"))
      (node (ref "IC5") (pin "4") (pinfunction "GND_4") (pintype "power_in"))
      (node (ref "IC7") (pin "1") (pinfunction "OE_1") (pintype "input"))
      (node (ref "IC7") (pin "3") (pinfunction "GND_3") (pintype "power_in"))
      (node (ref "IC8") (pin "1") (pinfunction "OE_1") (pintype "input"))
      (node (ref "IC8") (pin "3") (pinfunction "GND_3") (pintype "power_in"))
      (node (ref "IC9") (pin "1") (pinfunction "GND_1") (pintype "passive"))
      (node (ref "J1") (pin "GND") (pinfunction "1_GND") (pintype "passive"))
      (node (ref "J1") (pin "GND2") (pinfunction "4_GND2") (pintype "passive"))
      (node (ref "J2") (pin "GND") (pinfunction "1_GND") (pintype "passive"))
      (node (ref "J2") (pin "GND2") (pinfunction "4_GND2") (pintype "passive"))
      (node (ref "J3") (pin "GND") (pinfunction "1_GND") (pintype "passive"))
      (node (ref "J3") (pin "GND2") (pinfunction "4_GND2") (pintype "passive"))
      (node (ref "J4") (pin "GND") (pinfunction "1_GND") (pintype "passive"))
      (node (ref "J4") (pin "GND2") (pinfunction "4_GND2") (pintype "passive"))
      (node (ref "J5") (pin "GND") (pinfunction "1_GND") (pintype "passive"))
      (node (ref "J5") (pin "GND2") (pinfunction "4_GND2") (pintype "passive"))
      (node (ref "J6") (pin "GND") (pinfunction "1_GND") (pintype "passive"))
      (node (ref "J6") (pin "GND2") (pinfunction "4_GND2") (pintype "passive"))
      (node (ref "J7") (pin "GND") (pinfunction "1_GND") (pintype "passive"))
      (node (ref "J7") (pin "GND2") (pinfunction "4_GND2") (pintype "passive"))
      (node (ref "J8") (pin "GND") (pinfunction "1_GND") (pintype "passive"))
      (node (ref "J8") (pin "GND2") (pinfunction "4_GND2") (pintype "passive"))
      (node (ref "JP2") (pin "3") (pinfunction "3_3") (pintype "passive"))
      (node (ref "JP2") (pin "4") (pinfunction "4_4") (pintype "passive"))
      (node (ref "JP2") (pin "5") (pinfunction "5_5") (pintype "passive"))
      (node (ref "JP2") (pin "6") (pinfunction "6_6") (pintype "passive"))
      (node (ref "JP2") (pin "7") (pinfunction "7_7") (pintype "passive"))
      (node (ref "JP2") (pin "8") (pinfunction "8_8") (pintype "passive"))
      (node (ref "JP4") (pin "3") (pinfunction "3_3") (pintype "passive"))
      (node (ref "JP4") (pin "5") (pinfunction "5_5") (pintype "passive"))
      (node (ref "JP4") (pin "9") (pinfunction "9_9") (pintype "passive"))
      (node (ref "LED1") (pin "K") (pinfunction "C_K") (pintype "passive"))
      (node (ref "LED2") (pin "K") (pinfunction "C_K") (pintype "passive"))
      (node (ref "LED3") (pin "K") (pinfunction "C_K") (pintype "passive"))
      (node (ref "LED4") (pin "K") (pinfunction "C_K") (pintype "passive"))
      (node (ref "OK1") (pin "5") (pinfunction "GND_5") (pintype "passive"))
      (node (ref "Q1") (pin "E") (pinfunction "E_E") (pintype "passive"))
      (node (ref "Q2") (pin "E") (pinfunction "E_E") (pintype "passive"))
      (node (ref "R22") (pin "1") (pinfunction "1_1") (pintype "passive"))
      (node (ref "SW1") (pin "C") (pinfunction "C_C") (pintype "passive"))
      (node (ref "SW1") (pin "D") (pinfunction "1_D") (pintype "passive"))
      (node (ref "SW2") (pin "B1") (pinfunction "P_B1") (pintype "passive"))
      (node (ref "SW2") (pin "B2") (pinfunction "P1_B2") (pintype "passive"))
      (node (ref "SW3") (pin "B1") (pinfunction "P_B1") (pintype "passive"))
      (node (ref "SW3") (pin "B2") (pinfunction "P1_B2") (pintype "passive"))
      (node (ref "SW4") (pin "B1") (pinfunction "P_B1") (pintype "passive"))
      (node (ref "SW4") (pin "B2") (pinfunction "P1_B2") (pintype "passive"))
      (node (ref "UC1") (pin "20") (pinfunction "PB2/BOOT1_20") (pintype "bidirectional"))
      (node (ref "UC1") (pin "23") (pinfunction "VSS_1_23") (pintype "power_in"))
      (node (ref "UC1") (pin "35") (pinfunction "VSS_2_35") (pintype "power_in"))
      (node (ref "UC1") (pin "44") (pinfunction "BOOT0_44") (pintype "input"))
      (node (ref "UC1") (pin "47") (pinfunction "VSS_3_47") (pintype "power_in"))
      (node (ref "UC1") (pin "8") (pinfunction "VSS_A_8") (pintype "power_in"))
      (node (ref "X2") (pin "2") (pinfunction "2_2") (pintype "passive"))
    )
    (net (code "24") (name "JTCK") (class "Default")
      (node (ref "JP4") (pin "4") (pinfunction "4_4") (pintype "passive"))
      (node (ref "UC1") (pin "37") (pinfunction "PA14/JTCK/SWCLK_37") (pintype "bidirectional"))
    )
    (net (code "25") (name "JTDI") (class "Default")
      (node (ref "JP4") (pin "8") (pinfunction "8_8") (pintype "passive"))
      (node (ref "UC1") (pin "38") (pinfunction "PA15/JTDI_38") (pintype "bidirectional"))
    )
    (net (code "26") (name "JTDO") (class "Default")
      (node (ref "JP4") (pin "6") (pinfunction "6_6") (pintype "passive"))
      (node (ref "UC1") (pin "39") (pinfunction "PB3/JTDO_39") (pintype "bidirectional"))
    )
    (net (code "27") (name "JTMS") (class "Default")
      (node (ref "JP4") (pin "2") (pinfunction "2_2") (pintype "passive"))
      (node (ref "UC1") (pin "34") (pinfunction "PA13/JTMS/SWDIO_34") (pintype "bidirectional"))
    )
    (net (code "28") (name "LED_1") (class "Default")
      (node (ref "R33") (pin "1") (pinfunction "1_1") (pintype "passive"))
      (node (ref "UC1") (pin "33") (pinfunction "PA12/USART1_RTS/CAN_TX/TIM1_ETR/USBDP_33") (pintype "bidirectional"))
    )
    (net (code "29") (name "LED_2") (class "Default")
      (node (ref "R36") (pin "1") (pinfunction "1_1") (pintype "passive"))
      (node (ref "UC1") (pin "32") (pinfunction "PA11/USART1_CTS/CAN_RX/TIM1_CH4/USBDM_32") (pintype "bidirectional"))
    )
    (net (code "30") (name "LED_3") (class "Default")
      (node (ref "R41") (pin "1") (pinfunction "1_1") (pintype "passive"))
      (node (ref "UC1") (pin "29") (pinfunction "PA8/USART1_CK/TIM1_CH1/MCO_29") (pintype "bidirectional"))
    )
    (net (code "31") (name "LED_4") (class "Default")
      (node (ref "R42") (pin "1") (pinfunction "1_1") (pintype "passive"))
      (node (ref "UC1") (pin "27") (pinfunction "PB14/SPI2_MISO/USART3_RTS/TIM1_CH2N_27") (pintype "input"))
    )
    (net (code "32") (name "MIDI_RX") (class "Default")
      (node (ref "OK1") (pin "6") (pinfunction "VO_6") (pintype "passive"))
      (node (ref "R37") (pin "1") (pinfunction "1_1") (pintype "passive"))
      (node (ref "UC1") (pin "31") (pinfunction "PA10/USART1_RX/TIM1_CH3_31") (pintype "bidirectional"))
    )
    (net (code "33") (name "MIDI_TX") (class "Default")
      (node (ref "R40") (pin "2") (pinfunction "2_2") (pintype "passive"))
      (node (ref "UC1") (pin "30") (pinfunction "PA9/USART1_TX/TIM1_CH2_30") (pintype "input"))
    )
    (net (code "34") (name "Net-(D1-PadA)") (class "Default")
      (node (ref "D1") (pin "A") (pinfunction "A_A") (pintype "passive"))
      (node (ref "JP2") (pin "1") (pinfunction "1_1") (pintype "passive"))
      (node (ref "JP2") (pin "2") (pinfunction "2_2") (pintype "passive"))
    )
    (net (code "35") (name "Net-(D2-PadC)") (class "Default")
      (node (ref "D2") (pin "C") (pinfunction "C_C") (pintype "passive"))
      (node (ref "JP2") (pin "10") (pinfunction "10_10") (pintype "passive"))
      (node (ref "JP2") (pin "9") (pinfunction "9_9") (pintype "passive"))
    )
    (net (code "36") (name "Net-(DISP1-A)") (class "Default")
      (node (ref "DISP1") (pin "12") (pinfunction "A_12") (pintype "passive"))
      (node (ref "R3") (pin "2") (pinfunction "2_2") (pintype "passive"))
    )
    (net (code "37") (name "Net-(DISP1-B)") (class "Default")
      (node (ref "DISP1") (pin "10") (pinfunction "B_10") (pintype "passive"))
      (node (ref "R2") (pin "2") (pinfunction "2_2") (pintype "passive"))
    )
    (net (code "38") (name "Net-(DISP1-C)") (class "Default")
      (node (ref "DISP1") (pin "9") (pinfunction "C_9") (pintype "passive"))
      (node (ref "R10") (pin "2") (pinfunction "2_2") (pintype "passive"))
    )
    (net (code "39") (name "Net-(DISP1-D)") (class "Default")
      (node (ref "DISP1") (pin "7") (pinfunction "D_7") (pintype "passive"))
      (node (ref "R11") (pin "2") (pinfunction "2_2") (pintype "passive"))
    )
    (net (code "40") (name "Net-(DISP1-E)") (class "Default")
      (node (ref "DISP1") (pin "1") (pinfunction "E_1") (pintype "passive"))
      (node (ref "R16") (pin "2") (pinfunction "2_2") (pintype "passive"))
    )
    (net (code "41") (name "Net-(DISP1-F)") (class "Default")
      (node (ref "DISP1") (pin "18") (pinfunction "F_18") (pintype "passive"))
      (node (ref "R8") (pin "2") (pinfunction "2_2") (pintype "passive"))
    )
    (net (code "42") (name "Net-(DISP1-G)") (class "Default")
      (node (ref "DISP1") (pin "17") (pinfunction "G_17") (pintype "passive"))
      (node (ref "R7") (pin "2") (pinfunction "2_2") (pintype "passive"))
    )
    (net (code "43") (name "Net-(DISP1-H)") (class "Default")
      (node (ref "DISP1") (pin "15") (pinfunction "H_15") (pintype "passive"))
      (node (ref "R6") (pin "2") (pinfunction "2_2") (pintype "passive"))
    )
    (net (code "44") (name "Net-(DISP1-J)") (class "Default")
      (node (ref "DISP1") (pin "14") (pinfunction "J_14") (pintype "passive"))
      (node (ref "R5") (pin "2") (pinfunction "2_2") (pintype "passive"))
    )
    (net (code "45") (name "Net-(DISP1-K)") (class "Default")
      (node (ref "DISP1") (pin "6") (pinfunction "K_6") (pintype "passive"))
      (node (ref "R12") (pin "2") (pinfunction "2_2") (pintype "passive"))
    )
    (net (code "46") (name "Net-(DISP1-K1)") (class "Default")
      (node (ref "DISP1") (pin "16") (pinfunction "K1_16") (pintype "passive"))
      (node (ref "Q2") (pin "C") (pinfunction "C_C") (pintype "passive"))
    )
    (net (code "47") (name "Net-(DISP1-K2)") (class "Default")
      (node (ref "DISP1") (pin "11") (pinfunction "K2_11") (pintype "passive"))
      (node (ref "Q1") (pin "C") (pinfunction "C_C") (pintype "passive"))
    )
    (net (code "48") (name "Net-(DISP1-L)") (class "Default")
      (node (ref "DISP1") (pin "5") (pinfunction "L_5") (pintype "passive"))
      (node (ref "R13") (pin "2") (pinfunction "2_2") (pintype "passive"))
    )
    (net (code "49") (name "Net-(DISP1-M)") (class "Default")
      (node (ref "DISP1") (pin "4") (pinfunction "M_4") (pintype "passive"))
      (node (ref "R14") (pin "2") (pinfunction "2_2") (pintype "passive"))
    )
    (net (code "50") (name "Net-(DISP1-N)") (class "Default")
      (node (ref "DISP1") (pin "2") (pinfunction "N_2") (pintype "passive"))
      (node (ref "R15") (pin "2") (pinfunction "2_2") (pintype "passive"))
    )
    (net (code "51") (name "Net-(DISP1-P)") (class "Default")
      (node (ref "DISP1") (pin "13") (pinfunction "P_13") (pintype "passive"))
      (node (ref "R4") (pin "2") (pinfunction "2_2") (pintype "passive"))
    )
    (net (code "52") (name "Net-(IC2A-QA)") (class "Default")
      (node (ref "IC2") (pin "15") (pinfunction "QA_15") (pintype "tri_state"))
      (node (ref "R3") (pin "1") (pinfunction "1_1") (pintype "passive"))
    )
    (net (code "53") (name "Net-(IC2A-QB)") (class "Default")
      (node (ref "IC2") (pin "1") (pinfunction "QB_1") (pintype "tri_state"))
      (node (ref "R2") (pin "1") (pinfunction "1_1") (pintype "passive"))
    )
    (net (code "54") (name "Net-(IC2A-QC)") (class "Default")
      (node (ref "IC2") (pin "2") (pinfunction "QC_2") (pintype "tri_state"))
      (node (ref "R10") (pin "1") (pinfunction "1_1") (pintype "passive"))
    )
    (net (code "55") (name "Net-(IC2A-QD)") (class "Default")
      (node (ref "IC2") (pin "3") (pinfunction "QD_3") (pintype "tri_state"))
      (node (ref "R11") (pin "1") (pinfunction "1_1") (pintype "passive"))
    )
    (net (code "56") (name "Net-(IC2A-QE)") (class "Default")
      (node (ref "IC2") (pin "4") (pinfunction "QE_4") (pintype "tri_state"))
      (node (ref "R16") (pin "1") (pinfunction "1_1") (pintype "passive"))
    )
    (net (code "57") (name "Net-(IC2A-QF)") (class "Default")
      (node (ref "IC2") (pin "5") (pinfunction "QF_5") (pintype "tri_state"))
      (node (ref "R8") (pin "1") (pinfunction "1_1") (pintype "passive"))
    )
    (net (code "58") (name "Net-(IC2A-QG)") (class "Default")
      (node (ref "IC2") (pin "6") (pinfunction "QG_6") (pintype "tri_state"))
      (node (ref "R7") (pin "1") (pinfunction "1_1") (pintype "passive"))
    )
    (net (code "59") (name "Net-(IC2A-QH)") (class "Default")
      (node (ref "IC2") (pin "7") (pinfunction "QH_7") (pintype "tri_state"))
      (node (ref "R6") (pin "1") (pinfunction "1_1") (pintype "passive"))
    )
    (net (code "60") (name "Net-(IC2A-QH*)") (class "Default")
      (node (ref "IC2") (pin "9") (pinfunction "QH*_9") (pintype "tri_state"))
      (node (ref "IC3") (pin "14") (pinfunction "SER_14") (pintype "input"))
    )
    (net (code "61") (name "Net-(IC3A-QA)") (class "Default")
      (node (ref "IC3") (pin "15") (pinfunction "QA_15") (pintype "tri_state"))
      (node (ref "R5") (pin "1") (pinfunction "1_1") (pintype "passive"))
    )
    (net (code "62") (name "Net-(IC3A-QB)") (class "Default")
      (node (ref "IC3") (pin "1") (pinfunction "QB_1") (pintype "tri_state"))
      (node (ref "R12") (pin "1") (pinfunction "1_1") (pintype "passive"))
    )
    (net (code "63") (name "Net-(IC3A-QC)") (class "Default")
      (node (ref "IC3") (pin "2") (pinfunction "QC_2") (pintype "tri_state"))
      (node (ref "R13") (pin "1") (pinfunction "1_1") (pintype "passive"))
    )
    (net (code "64") (name "Net-(IC3A-QD)") (class "Default")
      (node (ref "IC3") (pin "3") (pinfunction "QD_3") (pintype "tri_state"))
      (node (ref "R14") (pin "1") (pinfunction "1_1") (pintype "passive"))
    )
    (net (code "65") (name "Net-(IC3A-QE)") (class "Default")
      (node (ref "IC3") (pin "4") (pinfunction "QE_4") (pintype "tri_state"))
      (node (ref "R15") (pin "1") (pinfunction "1_1") (pintype "passive"))
    )
    (net (code "66") (name "Net-(IC3A-QF)") (class "Default")
      (node (ref "IC3") (pin "5") (pinfunction "QF_5") (pintype "tri_state"))
      (node (ref "R4") (pin "1") (pinfunction "1_1") (pintype "passive"))
    )
    (net (code "67") (name "Net-(IC6A--IN)") (class "Default")
      (node (ref "C14") (pin "1") (pinfunction "1_1") (pintype "passive"))
      (node (ref "IC6") (pin "2") (pinfunction "-IN_2") (pintype "input"))
      (node (ref "R18") (pin "1") (pinfunction "1_1") (pintype "passive"))
      (node (ref "R26") (pin "2") (pinfunction "2_2") (pintype "passive"))
    )
    (net (code "68") (name "Net-(IC6A-OUT)") (class "Default")
      (node (ref "C14") (pin "2") (pinfunction "2_2") (pintype "passive"))
      (node (ref "IC6") (pin "1") (pinfunction "OUT_1") (pintype "output"))
      (node (ref "R24") (pin "2") (pinfunction "2_2") (pintype "passive"))
    )
    (net (code "69") (name "Net-(IC6B--IN)") (class "Default")
      (node (ref "C21") (pin "1") (pinfunction "1_1") (pintype "passive"))
      (node (ref "IC6") (pin "6") (pinfunction "-IN_6") (pintype "input"))
      (node (ref "R19") (pin "1") (pinfunction "1_1") (pintype "passive"))
      (node (ref "R28") (pin "2") (pinfunction "2_2") (pintype "passive"))
    )
    (net (code "70") (name "Net-(IC6B-OUT)") (class "Default")
      (node (ref "C21") (pin "2") (pinfunction "2_2") (pintype "passive"))
      (node (ref "IC6") (pin "7") (pinfunction "OUT_7") (pintype "output"))
      (node (ref "R30") (pin "2") (pinfunction "2_2") (pintype "passive"))
    )
    (net (code "71") (name "Net-(IC6C--IN)") (class "Default")
      (node (ref "C22") (pin "1") (pinfunction "1_1") (pintype "passive"))
      (node (ref "IC6") (pin "9") (pinfunction "-IN_9") (pintype "input"))
      (node (ref "R20") (pin "1") (pinfunction "1_1") (pintype "passive"))
      (node (ref "R29") (pin "2") (pinfunction "2_2") (pintype "passive"))
    )
    (net (code "72") (name "Net-(IC6C-OUT)") (class "Default")
      (node (ref "C22") (pin "2") (pinfunction "2_2") (pintype "passive"))
      (node (ref "IC6") (pin "8") (pinfunction "OUT_8") (pintype "output"))
      (node (ref "R31") (pin "2") (pinfunction "2_2") (pintype "passive"))
    )
    (net (code "73") (name "Net-(IC6D--IN)") (class "Default")
      (node (ref "C16") (pin "1") (pinfunction "1_1") (pintype "passive"))
      (node (ref "IC6") (pin "13") (pinfunction "-IN_13") (pintype "input"))
      (node (ref "R21") (pin "1") (pinfunction "1_1") (pintype "passive"))
      (node (ref "R27") (pin "2") (pinfunction "2_2") (pintype "passive"))
    )
    (net (code "74") (name "Net-(IC6D-OUT)") (class "Default")
      (node (ref "C16") (pin "2") (pinfunction "2_2") (pintype "passive"))
      (node (ref "IC6") (pin "14") (pinfunction "OUT_14") (pintype "output"))
      (node (ref "R25") (pin "2") (pinfunction "2_2") (pintype "passive"))
    )
    (net (code "75") (name "Net-(IC7A-O)") (class "Default")
      (node (ref "IC7") (pin "4") (pinfunction "O_4") (pintype "tri_state"))
      (node (ref "R32") (pin "2") (pinfunction "2_2") (pintype "passive"))
    )
    (net (code "76") (name "Net-(IC8A-O)") (class "Default")
      (node (ref "IC8") (pin "4") (pinfunction "O_4") (pintype "tri_state"))
      (node (ref "R34") (pin "2") (pinfunction "2_2") (pintype "passive"))
    )
    (net (code "77") (name "Net-(IC10A-O)") (class "Default")
      (node (ref "IC10") (pin "4") (pinfunction "O_4") (pintype "tri_state"))
      (node (ref "R38") (pin "2") (pinfunction "2_2") (pintype "passive"))
    )
    (net (code "78") (name "Net-(IC11A-O)") (class "Default")
      (node (ref "IC11") (pin "4") (pinfunction "O_4") (pintype "tri_state"))
      (node (ref "R43") (pin "2") (pinfunction "2_2") (pintype "passive"))
    )
    (net (code "79") (name "Net-(J1-2)") (class "Default")
      (node (ref "J1") (pin "TIP") (pinfunction "2_TIP") (pintype "passive"))
      (node (ref "R25") (pin "1") (pinfunction "1_1") (pintype "passive"))
      (node (ref "R27") (pin "1") (pinfunction "1_1") (pintype "passive"))
    )
    (net (code "80") (name "Net-(J2-2)") (class "Default")
      (node (ref "J2") (pin "TIP") (pinfunction "2_TIP") (pintype "passive"))
      (node (ref "R32") (pin "1") (pinfunction "1_1") (pintype "passive"))
    )
    (net (code "81") (name "Net-(J3-2)") (class "Default")
      (node (ref "J3") (pin "TIP") (pinfunction "2_TIP") (pintype "passive"))
      (node (ref "R29") (pin "1") (pinfunction "1_1") (pintype "passive"))
      (node (ref "R31") (pin "1") (pinfunction "1_1") (pintype "passive"))
    )
    (net (code "82") (name "Net-(J4-2)") (class "Default")
      (node (ref "J4") (pin "TIP") (pinfunction "2_TIP") (pintype "passive"))
      (node (ref "R34") (pin "1") (pinfunction "1_1") (pintype "passive"))
    )
    (net (code "83") (name "Net-(J5-2)") (class "Default")
      (node (ref "J5") (pin "TIP") (pinfunction "2_TIP") (pintype "passive"))
      (node (ref "R28") (pin "1") (pinfunction "1_1") (pintype "passive"))
      (node (ref "R30") (pin "1") (pinfunction "1_1") (pintype "passive"))
    )
    (net (code "84") (name "Net-(J6-2)") (class "Default")
      (node (ref "J6") (pin "TIP") (pinfunction "2_TIP") (pintype "passive"))
      (node (ref "R38") (pin "1") (pinfunction "1_1") (pintype "passive"))
    )
    (net (code "85") (name "Net-(J7-2)") (class "Default")
      (node (ref "J7") (pin "TIP") (pinfunction "2_TIP") (pintype "passive"))
      (node (ref "R24") (pin "1") (pinfunction "1_1") (pintype "passive"))
      (node (ref "R26") (pin "1") (pinfunction "1_1") (pintype "passive"))
    )
    (net (code "86") (name "Net-(J8-2)") (class "Default")
      (node (ref "J8") (pin "TIP") (pinfunction "2_TIP") (pintype "passive"))
      (node (ref "R43") (pin "1") (pinfunction "1_1") (pintype "passive"))
    )
    (net (code "87") (name "Net-(LED1-PadA)") (class "Default")
      (node (ref "LED1") (pin "A") (pinfunction "A_A") (pintype "passive"))
      (node (ref "R33") (pin "2") (pinfunction "2_2") (pintype "passive"))
    )
    (net (code "88") (name "Net-(LED2-PadA)") (class "Default")
      (node (ref "LED2") (pin "A") (pinfunction "A_A") (pintype "passive"))
      (node (ref "R36") (pin "2") (pinfunction "2_2") (pintype "passive"))
    )
    (net (code "89") (name "Net-(LED3-PadA)") (class "Default")
      (node (ref "LED3") (pin "A") (pinfunction "A_A") (pintype "passive"))
      (node (ref "R41") (pin "2") (pinfunction "2_2") (pintype "passive"))
    )
    (net (code "90") (name "Net-(LED4-PadA)") (class "Default")
      (node (ref "LED4") (pin "A") (pinfunction "A_A") (pintype "passive"))
      (node (ref "R42") (pin "2") (pinfunction "2_2") (pintype "passive"))
    )
    (net (code "91") (name "Net-(OK1-A)") (class "Default")
      (node (ref "D3") (pin "C") (pinfunction "C_C") (pintype "passive"))
      (node (ref "OK1") (pin "2") (pinfunction "A_2") (pintype "passive"))
      (node (ref "R35") (pin "1") (pinfunction "1_1") (pintype "passive"))
    )
    (net (code "92") (name "Net-(OK1-C)") (class "Default")
      (node (ref "D3") (pin "A") (pinfunction "A_A") (pintype "passive"))
      (node (ref "OK1") (pin "3") (pinfunction "C_3") (pintype "passive"))
      (node (ref "X1") (pin "5") (pinfunction "5_5") (pintype "passive"))
    )
    (net (code "93") (name "Net-(Q1-PadB)") (class "Default")
      (node (ref "Q1") (pin "B") (pinfunction "B_B") (pintype "passive"))
      (node (ref "R1") (pin "2") (pinfunction "2_2") (pintype "passive"))
    )
    (net (code "94") (name "Net-(Q2-PadB)") (class "Default")
      (node (ref "Q2") (pin "B") (pinfunction "B_B") (pintype "passive"))
      (node (ref "R9") (pin "2") (pinfunction "2_2") (pintype "passive"))
    )
    (net (code "95") (name "Net-(R35-Pad2)") (class "Default")
      (node (ref "R35") (pin "2") (pinfunction "2_2") (pintype "passive"))
      (node (ref "X1") (pin "4") (pinfunction "4_4") (pintype "passive"))
    )
    (net (code "96") (name "Net-(R39-Pad1)") (class "Default")
      (node (ref "R39") (pin "1") (pinfunction "1_1") (pintype "passive"))
      (node (ref "X2") (pin "4") (pinfunction "4_4") (pintype "passive"))
    )
    (net (code "97") (name "Net-(R40-Pad1)") (class "Default")
      (node (ref "R40") (pin "1") (pinfunction "1_1") (pintype "passive"))
      (node (ref "X2") (pin "5") (pinfunction "5_5") (pintype "passive"))
    )
    (net (code "98") (name "Net-(UC1-PD0-OSC_IN)") (class "Default")
      (node (ref "C7") (pin "2") (pinfunction "2_2") (pintype "passive"))
      (node (ref "Q3") (pin "2") (pinfunction "2_2") (pintype "passive"))
      (node (ref "UC1") (pin "5") (pinfunction "PD0-OSC_IN_5") (pintype "input"))
    )
    (net (code "99") (name "Net-(UC1-PD1-OSC_OUT)") (class "Default")
      (node (ref "C10") (pin "2") (pinfunction "2_2") (pintype "passive"))
      (node (ref "Q3") (pin "1") (pinfunction "1_1") (pintype "passive"))
      (node (ref "UC1") (pin "6") (pinfunction "PD1-OSC_OUT_6") (pintype "input"))
    )
    (net (code "100") (name "RESET") (class "Default")
      (node (ref "JP4") (pin "10") (pinfunction "10_10") (pintype "passive"))
      (node (ref "R17") (pin "1") (pinfunction "1_1") (pintype "passive"))
      (node (ref "UC1") (pin "7") (pinfunction "NRST_7") (pintype "input"))
    )
    (net (code "101") (name "SWITCH_0") (class "Default")
      (node (ref "SW2") (pin "A1") (pinfunction "S_A1") (pintype "passive"))
      (node (ref "SW2") (pin "A2") (pinfunction "S1_A2") (pintype "passive"))
      (node (ref "UC1") (pin "15") (pinfunction "PA5/SPI1_SCK/ADC12_IN5_15") (pintype "bidirectional"))
    )
    (net (code "102") (name "SWITCH_1") (class "Default")
      (node (ref "SW3") (pin "A1") (pinfunction "S_A1") (pintype "passive"))
      (node (ref "SW3") (pin "A2") (pinfunction "S1_A2") (pintype "passive"))
      (node (ref "UC1") (pin "16") (pinfunction "PA6/SPI1_MISO/ADC12_IN6/TIM3_CH1_16") (pintype "bidirectional"))
    )
    (net (code "103") (name "SWITCH_2") (class "Default")
      (node (ref "SW4") (pin "A1") (pinfunction "S_A1") (pintype "passive"))
      (node (ref "SW4") (pin "A2") (pinfunction "S1_A2") (pintype "passive"))
      (node (ref "UC1") (pin "14") (pinfunction "PA4/SPI1_NSS/USART2_CK/ADC12_IN4_14") (pintype "bidirectional"))
    )
    (net (code "104") (name "VCC") (class "Default")
      (node (ref "C1") (pin "+") (pinfunction "+_+") (pintype "passive"))
      (node (ref "C12") (pin "+") (pinfunction "+_+") (pintype "passive"))
      (node (ref "C19") (pin "1") (pinfunction "1_1") (pintype "passive"))
      (node (ref "C25") (pin "1") (pinfunction "1_1") (pintype "passive"))
      (node (ref "D1") (pin "C") (pinfunction "C_C") (pintype "passive"))
      (node (ref "IC1") (pin "3") (pinfunction "VIN_3") (pintype "input"))
      (node (ref "IC5") (pin "2") (pinfunction "V+_2") (pintype "power_in"))
      (node (ref "IC6") (pin "4") (pinfunction "V+_4") (pintype "power_in"))
      (node (ref "IC9") (pin "3") (pinfunction "VI_3") (pintype "input"))
    )
    (net (code "105") (name "VEE") (class "Default")
      (node (ref "C20") (pin "2") (pinfunction "2_2") (pintype "passive"))
      (node (ref "C3") (pin "-") (pinfunction "-_-") (pintype "passive"))
      (node (ref "D2") (pin "A") (pinfunction "A_A") (pintype "passive"))
      (node (ref "IC6") (pin "11") (pinfunction "V-_11") (pintype "power_in"))
    )
    (net (code "106") (name "VREF") (class "Default")
      (node (ref "C17") (pin "1") (pinfunction "1_1") (pintype "passive"))
      (node (ref "IC4") (pin "3") (pinfunction "VREFH_3") (pintype "bidirectional"))
      (node (ref "R23") (pin "2") (pinfunction "2_2") (pintype "passive"))
    )
    (net (code "107") (name "VREF{slash}2") (class "Default")
      (node (ref "IC6") (pin "10") (pinfunction "+IN_10") (pintype "input"))
      (node (ref "IC6") (pin "12") (pinfunction "+IN_12") (pintype "input"))
      (node (ref "IC6") (pin "3") (pinfunction "+IN_3") (pintype "input"))
      (node (ref "IC6") (pin "5") (pinfunction "+IN_5") (pintype "input"))
      (node (ref "R22") (pin "2") (pinfunction "2_2") (pintype "passive"))
      (node (ref "R23") (pin "1") (pinfunction "1_1") (pintype "passive"))
    )
    (net (code "108") (name "unconnected-(DISP1-DP-Pad8)") (class "Default")
      (node (ref "DISP1") (pin "8") (pinfunction "DP_8") (pintype "passive"))
    )
    (net (code "109") (name "unconnected-(IC3A-QG-Pad6)") (class "Default")
      (node (ref "IC3") (pin "6") (pinfunction "QG_6") (pintype "tri_state"))
    )
    (net (code "110") (name "unconnected-(IC3A-QH*-Pad9)") (class "Default")
      (node (ref "IC3") (pin "9") (pinfunction "QH*_9") (pintype "tri_state"))
    )
    (net (code "111") (name "unconnected-(IC3A-QH-Pad7)") (class "Default")
      (node (ref "IC3") (pin "7") (pinfunction "QH_7") (pintype "tri_state"))
    )
    (net (code "112") (name "unconnected-(IC5-OPT-Pad3)") (class "Default")
      (node (ref "IC5") (pin "3") (pinfunction "OPT_3") (pintype "output"))
    )
    (net (code "113") (name "unconnected-(IC5-TRM-Pad5)") (class "Default")
      (node (ref "IC5") (pin "5") (pinfunction "TRM_5") (pintype "input"))
    )
    (net (code "114") (name "unconnected-(J1-3-PadSW)") (class "Default")
      (node (ref "J1") (pin "SW") (pinfunction "3_SW") (pintype "passive"))
    )
    (net (code "115") (name "unconnected-(J2-3-PadSW)") (class "Default")
      (node (ref "J2") (pin "SW") (pinfunction "3_SW") (pintype "passive"))
    )
    (net (code "116") (name "unconnected-(J3-3-PadSW)") (class "Default")
      (node (ref "J3") (pin "SW") (pinfunction "3_SW") (pintype "passive"))
    )
    (net (code "117") (name "unconnected-(J4-3-PadSW)") (class "Default")
      (node (ref "J4") (pin "SW") (pinfunction "3_SW") (pintype "passive"))
    )
    (net (code "118") (name "unconnected-(J5-3-PadSW)") (class "Default")
      (node (ref "J5") (pin "SW") (pinfunction "3_SW") (pintype "passive"))
    )
    (net (code "119") (name "unconnected-(J6-3-PadSW)") (class "Default")
      (node (ref "J6") (pin "SW") (pinfunction "3_SW") (pintype "passive"))
    )
    (net (code "120") (name "unconnected-(J7-3-PadSW)") (class "Default")
      (node (ref "J7") (pin "SW") (pinfunction "3_SW") (pintype "passive"))
    )
    (net (code "121") (name "unconnected-(J8-3-PadSW)") (class "Default")
      (node (ref "J8") (pin "SW") (pinfunction "3_SW") (pintype "passive"))
    )
    (net (code "122") (name "unconnected-(JP4-Pad7)") (class "Default")
      (node (ref "JP4") (pin "7") (pinfunction "7_7") (pintype "passive"))
    )
    (net (code "123") (name "unconnected-(OK1-VE-Pad7)") (class "Default")
      (node (ref "OK1") (pin "7") (pinfunction "VE_7") (pintype "passive"))
    )
    (net (code "124") (name "unconnected-(UC1-PA0_WKUP{slash}USART2_CTS{slash}ADC12_IN0{slash}TIM2_CH1_ETR-Pad10)") (class "Default")
      (node (ref "UC1") (pin "10") (pinfunction "PA0_WKUP/USART2_CTS/ADC12_IN0/TIM2_CH1_ETR_10") (pintype "bidirectional"))
    )
    (net (code "125") (name "unconnected-(UC1-PA1{slash}USART2_RTS{slash}ADC12_IN1{slash}TIM2_CH2-Pad11)") (class "Default")
      (node (ref "UC1") (pin "11") (pinfunction "PA1/USART2_RTS/ADC12_IN1/TIM2_CH2_11") (pintype "bidirectional"))
    )
    (net (code "126") (name "unconnected-(UC1-PA2{slash}USART2_TX{slash}ADC12_IN2{slash}TIM2_CH3-Pad12)") (class "Default")
      (node (ref "UC1") (pin "12") (pinfunction "PA2/USART2_TX/ADC12_IN2/TIM2_CH3_12") (pintype "bidirectional"))
    )
    (net (code "127") (name "unconnected-(UC1-PA3{slash}USART2_RX{slash}ADC12_IN3{slash}TIM2_CH4-Pad13)") (class "Default")
      (node (ref "UC1") (pin "13") (pinfunction "PA3/USART2_RX/ADC12_IN3/TIM2_CH4_13") (pintype "bidirectional"))
    )
    (net (code "128") (name "unconnected-(UC1-PA7{slash}SPI1_MOSI{slash}ADC12_IN7{slash}TIM3_CH2-Pad17)") (class "Default")
      (node (ref "UC1") (pin "17") (pinfunction "PA7/SPI1_MOSI/ADC12_IN7/TIM3_CH2_17") (pintype "bidirectional"))
    )
    (net (code "129") (name "unconnected-(UC1-PB4{slash}NJTRST-Pad40)") (class "Default")
      (node (ref "UC1") (pin "40") (pinfunction "PB4/NJTRST_40") (pintype "bidirectional"))
    )
    (net (code "130") (name "unconnected-(X1-Pad1)") (class "Default")
      (node (ref "X1") (pin "1") (pinfunction "1_1") (pintype "passive"))
    )
    (net (code "131") (name "unconnected-(X1-Pad2)") (class "Default")
      (node (ref "X1") (pin "2") (pinfunction "2_2") (pintype "passive"))
    )
    (net (code "132") (name "unconnected-(X1-Pad3)") (class "Default")
      (node (ref "X1") (pin "3") (pinfunction "3_3") (pintype "passive"))
    )
    (net (code "133") (name "unconnected-(X2-Pad1)") (class "Default")
      (node (ref "X2") (pin "1") (pinfunction "1_1") (pintype "passive"))
    )
    (net (code "134") (name "unconnected-(X2-Pad3)") (class "Default")
      (node (ref "X2") (pin "3") (pinfunction "3_3") (pintype "passive"))
    )
  )
)
